# 12-SoC_POWER2.net
KiCad netlist of a schematic drawn in Altium Designer
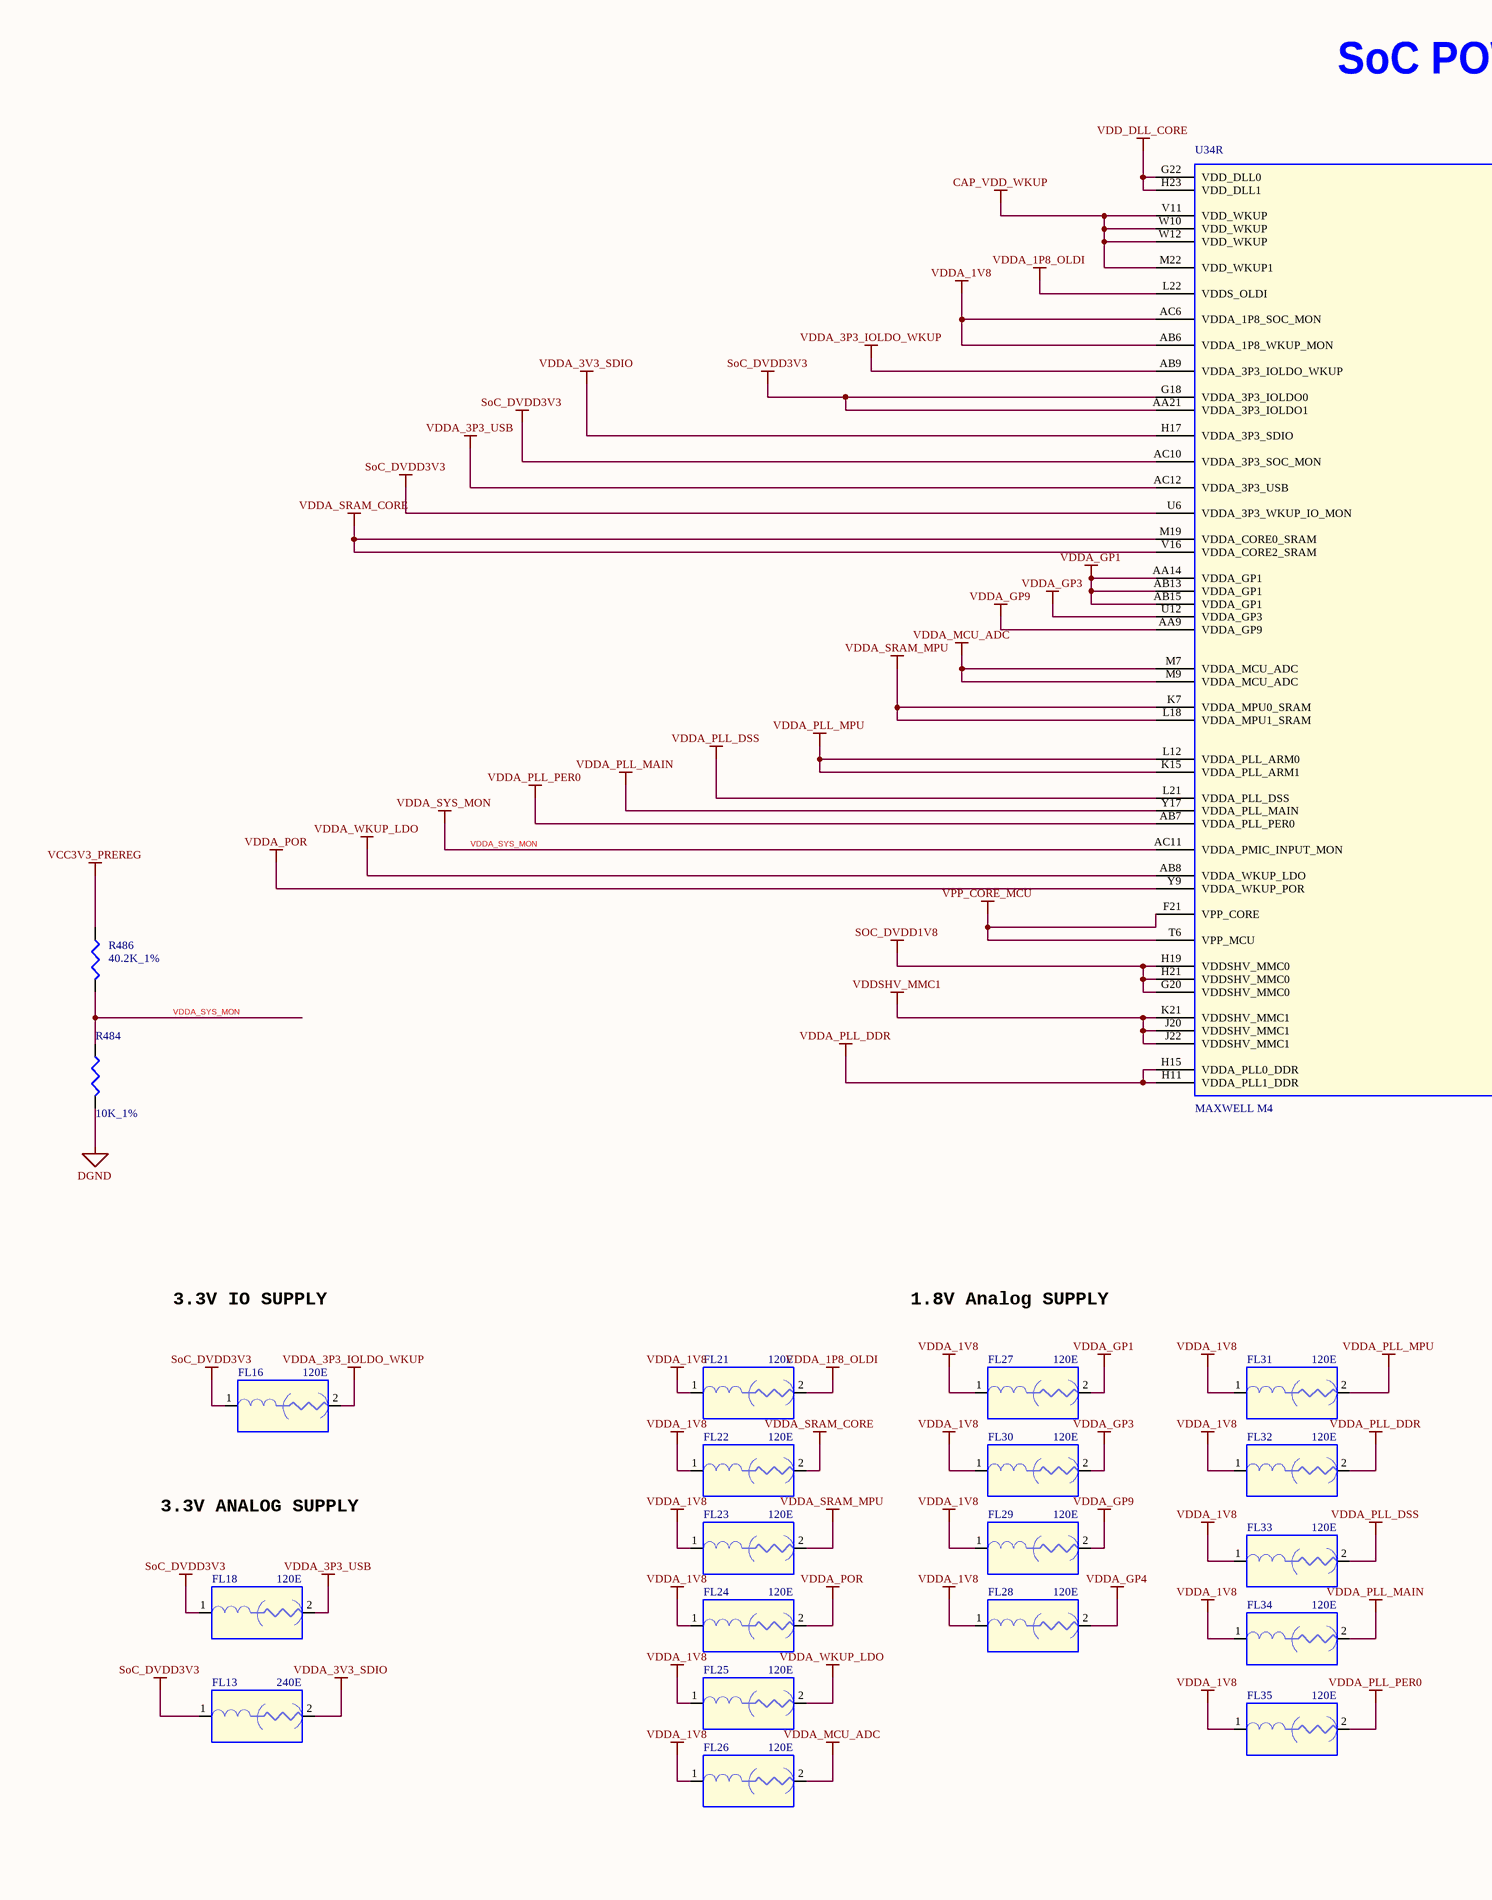
[diagram p0: 12-SoC POWER2.SchDoc, left]
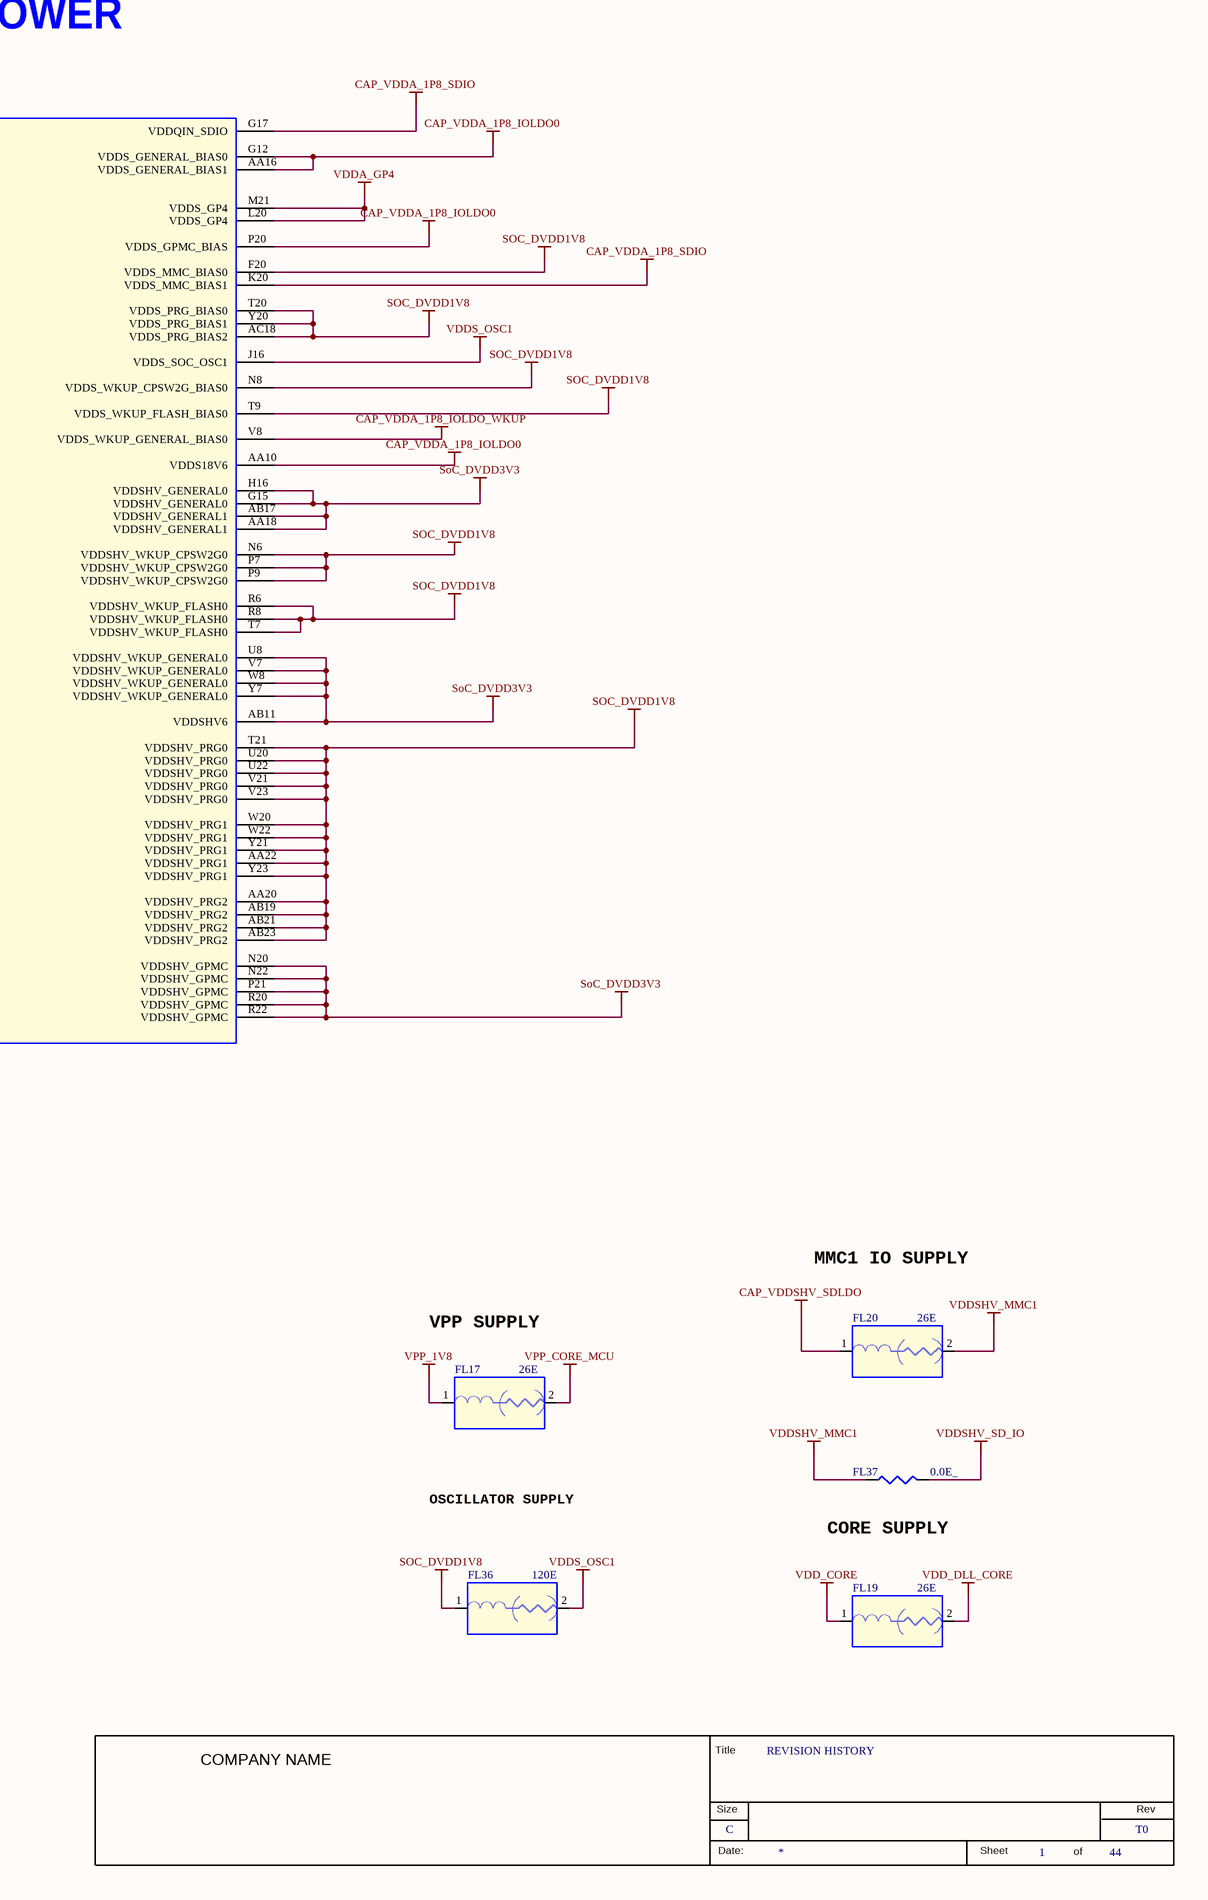
[diagram p1: 12-SoC POWER2.SchDoc, right]

(export (version "E")
  (design (tool "Eeschema 10.0.6"))
  (components
    (comp (ref "FL13")
      (value "240E")
      (footprint "EMIFIL_BLM03B_0201")
      (description "FERRITE CHIP 240E 350mA 0201")
      (fields
        (field (name "MISTRAL PART NO") "130014070021-R")
        (field (name "MFR_PART_NUMBER") "BLM03AX241SN1D")
      )
      (libsource (lib "*") (part "EMIFILTER_IND"))
    )
    (comp (ref "FL16")
      (value "120E")
      (footprint "EMIFIL_BLM18R_0603_1")
      (description "FERRITE BEAD 120E 2A 0603")
      (fields
        (field (name "MISTRAL PART NO") "130010060030-R")
        (field (name "MFR_PART_NUMBER") "BLM18EG121SN1D")
      )
      (libsource (lib "*") (part "EMIFILTER_IND"))
    )
    (comp (ref "FL17")
      (value "26E")
      (footprint "EMIFIL_BLM18K_0603")
      (description "FERRITE CHIP 26E 6A 0603")
      (fields
        (field (name "MISTRAL PART NO") "130012010003-R")
        (field (name "MFR_PART_NUMBER") "BLM18KG260TN1D")
      )
      (libsource (lib "*") (part "EMIFILTER_IND"))
    )
    (comp (ref "FL18")
      (value "120E")
      (footprint "EMIFIL_BLM18R_0603_1")
      (description "FERRITE BEAD 120E 2A 0603")
      (fields
        (field (name "MISTRAL PART NO") "130010060030-R")
        (field (name "MFR_PART_NUMBER") "BLM18EG121SN1D")
      )
      (libsource (lib "*") (part "EMIFILTER_IND"))
    )
    (comp (ref "FL19")
      (value "26E")
      (footprint "EMIFIL_BLM18K_0603")
      (description "FERRITE CHIP 26E 6A 0603")
      (fields (field (name "DISTRIBUTOR_PART_NUMBER") "490-5252-1-ND") (field (name "VOLTAGE") "NA"))
      (libsource (lib "*") (part "EMIFILTER_IND"))
    )
    (comp (ref "FL20")
      (value "26E")
      (footprint "EMIFIL_BLM18K_0603")
      (description "FERRITE CHIP 26E 6A 0603")
      (fields (field (name "DISTRIBUTOR_PART_NUMBER") "490-5252-1-ND") (field (name "VOLTAGE") "NA"))
      (libsource (lib "*") (part "EMIFILTER_IND"))
    )
    (comp (ref "FL21")
      (value "120E")
      (footprint "EMIFIL_BLM18R_0603_1")
      (description "FERRITE BEAD 120E 2A 0603")
      (fields
        (field (name "MISTRAL PART NO") "130010060030-R")
        (field (name "MFR_PART_NUMBER") "BLM18EG121SN1D")
      )
      (libsource (lib "*") (part "EMIFILTER_IND"))
    )
    (comp (ref "FL22")
      (value "120E")
      (footprint "EMIFIL_BLM18R_0603_1")
      (description "FERRITE BEAD 120E 2A 0603")
      (fields
        (field (name "MISTRAL PART NO") "130010060030-R")
        (field (name "MFR_PART_NUMBER") "BLM18EG121SN1D")
      )
      (libsource (lib "*") (part "EMIFILTER_IND"))
    )
    (comp (ref "FL23")
      (value "120E")
      (footprint "EMIFIL_BLM18R_0603_1")
      (description "FERRITE BEAD 120E 2A 0603")
      (fields
        (field (name "MISTRAL PART NO") "130010060030-R")
        (field (name "MFR_PART_NUMBER") "BLM18EG121SN1D")
      )
      (libsource (lib "*") (part "EMIFILTER_IND"))
    )
    (comp (ref "FL24")
      (value "120E")
      (footprint "EMIFIL_BLM18R_0603_1")
      (description "FERRITE BEAD 120E 2A 0603")
      (fields (field (name "DISTRIBUTOR_PART_NUMBER") "490-3991-1-ND") (field (name "VOLTAGE") "NA"))
      (libsource (lib "*") (part "EMIFILTER_IND"))
    )
    (comp (ref "FL25")
      (value "120E")
      (footprint "EMIFIL_BLM18R_0603_1")
      (description "FERRITE BEAD 120E 2A 0603")
      (fields
        (field (name "MISTRAL PART NO") "130010060030-R")
        (field (name "MFR_PART_NUMBER") "BLM18EG121SN1D")
      )
      (libsource (lib "*") (part "EMIFILTER_IND"))
    )
    (comp (ref "FL26")
      (value "120E")
      (footprint "EMIFIL_BLM18R_0603_1")
      (description "FERRITE BEAD 120E 2A 0603")
      (fields (field (name "DISTRIBUTOR_PART_NUMBER") "490-3991-1-ND") (field (name "VOLTAGE") "NA"))
      (libsource (lib "*") (part "EMIFILTER_IND"))
    )
    (comp (ref "FL27")
      (value "120E")
      (footprint "EMIFIL_BLM18R_0603_1")
      (description "FERRITE BEAD 120E 2A 0603")
      (fields
        (field (name "MISTRAL PART NO") "130010060030-R")
        (field (name "MFR_PART_NUMBER") "BLM18EG121SN1D")
      )
      (libsource (lib "*") (part "EMIFILTER_IND"))
    )
    (comp (ref "FL28")
      (value "120E")
      (footprint "EMIFIL_BLM18R_0603_1")
      (description "FERRITE BEAD 120E 2A 0603")
      (fields (field (name "DISTRIBUTOR_PART_NUMBER") "490-3991-1-ND") (field (name "VOLTAGE") "NA"))
      (libsource (lib "*") (part "EMIFILTER_IND"))
    )
    (comp (ref "FL29")
      (value "120E")
      (footprint "EMIFIL_BLM18R_0603_1")
      (description "FERRITE BEAD 120E 2A 0603")
      (fields (field (name "DISTRIBUTOR_PART_NUMBER") "490-3991-1-ND") (field (name "VOLTAGE") "NA"))
      (libsource (lib "*") (part "EMIFILTER_IND"))
    )
    (comp (ref "FL30")
      (value "120E")
      (footprint "EMIFIL_BLM18R_0603_1")
      (description "FERRITE BEAD 120E 2A 0603")
      (fields
        (field (name "MISTRAL PART NO") "130010060030-R")
        (field (name "MFR_PART_NUMBER") "BLM18EG121SN1D")
      )
      (libsource (lib "*") (part "EMIFILTER_IND"))
    )
    (comp (ref "FL31")
      (value "120E")
      (footprint "EMIFIL_BLM18R_0603_1")
      (description "FERRITE BEAD 120E 2A 0603")
      (fields (field (name "DISTRIBUTOR_PART_NUMBER") "490-3991-1-ND") (field (name "VOLTAGE") "NA"))
      (libsource (lib "*") (part "EMIFILTER_IND"))
    )
    (comp (ref "FL32")
      (value "120E")
      (footprint "EMIFIL_BLM18R_0603_1")
      (description "FERRITE BEAD 120E 2A 0603")
      (fields
        (field (name "MISTRAL PART NO") "130010060030-R")
        (field (name "MFR_PART_NUMBER") "BLM18EG121SN1D")
      )
      (libsource (lib "*") (part "EMIFILTER_IND"))
    )
    (comp (ref "FL33")
      (value "120E")
      (footprint "EMIFIL_BLM18R_0603_1")
      (description "FERRITE BEAD 120E 2A 0603")
      (fields
        (field (name "MISTRAL PART NO") "130010060030-R")
        (field (name "MFR_PART_NUMBER") "BLM18EG121SN1D")
      )
      (libsource (lib "*") (part "EMIFILTER_IND"))
    )
    (comp (ref "FL34")
      (value "120E")
      (footprint "EMIFIL_BLM18R_0603_1")
      (description "FERRITE BEAD 120E 2A 0603")
      (fields
        (field (name "MISTRAL PART NO") "130010060030-R")
        (field (name "MFR_PART_NUMBER") "BLM18EG121SN1D")
      )
      (libsource (lib "*") (part "EMIFILTER_IND"))
    )
    (comp (ref "FL35")
      (value "120E")
      (footprint "EMIFIL_BLM18R_0603_1")
      (description "FERRITE BEAD 120E 2A 0603")
      (fields
        (field (name "MISTRAL PART NO") "130010060030-R")
        (field (name "MFR_PART_NUMBER") "BLM18EG121SN1D")
      )
      (libsource (lib "*") (part "EMIFILTER_IND"))
    )
    (comp (ref "FL36")
      (value "120E")
      (footprint "EMIFIL_BLM18R_0603_1")
      (description "FERRITE BEAD 120E 2A 0603")
      (fields (field (name "DISTRIBUTOR_PART_NUMBER") "490-3991-1-ND") (field (name "VOLTAGE") "NA"))
      (libsource (lib "*") (part "EMIFILTER_IND"))
    )
    (comp (ref "FL37")
      (value "0.0E_")
      (footprint "RES0603")
      (description "RES 0.0E 1/10W 0603")
      (fields
        (field (name "MISTRAL PART NO") "110010020006-P")
        (field (name "MFR_PART_NUMBER") "CRCW06030000Z0EA")
      )
      (libsource (lib "*") (part "RESISTOR"))
    )
    (comp (ref "R484")
      (value "10K_1%")
      (footprint "RES0402_0-5")
      (description "RES 10K 1/16W 1% 0402")
      (fields (field (name "DISTRIBUTOR_PART_NUMBER") "311-10.0KLRTR-ND") (field (name "VOLTAGE") "NA"))
      (libsource (lib "*") (part "RESISTOR_Dup5"))
    )
    (comp (ref "R486")
      (value "40.2K_1%")
      (footprint "RES0402_0-5")
      (description "RES 40.2K 1/16W 1% 0402")
      (fields (field (name "DISTRIBUTOR_PART_NUMBER") "311-40.2KLRDKR-ND") (field (name "VOLTAGE") "NA"))
      (libsource (lib "*") (part "RESISTOR_Dup5"))
    )
    (comp (ref "U34")
      (value "MAXWELL M4")
      (footprint "BGA784_31-49_910X910_1-7")
      (description "IC MAXWELL MICRO CONTROLLER UNIT BGA784")
      (fields (field (name "DISTRIBUTOR_PART_NUMBER") "NA") (field (name "MFR_PART_NUMBER") "MAXWELL M4_EVM"))
      (libsource (lib "*") (part "AM654X_BGA784"))
    )
  )
  (nets
    (net (code "1") (name "CAP_VDDA_1P8_IOLDO0") (class "Default")
      (node (ref "U34") (pin "AA10") (pinfunction "VDDS18V6_AA10") (pintype "power_in"))
      (node (ref "U34") (pin "AA16") (pinfunction "VDDS_GENERAL_BIAS1_AA16") (pintype "power_in"))
      (node (ref "U34") (pin "G12") (pinfunction "VDDS_GENERAL_BIAS0_G12") (pintype "power_in"))
      (node (ref "U34") (pin "P20") (pinfunction "VDDS_GPMC_BIAS_P20") (pintype "power_in"))
    )
    (net (code "2") (name "CAP_VDDA_1P8_IOLDO_WKUP") (class "Default")
      (node (ref "U34") (pin "V8") (pinfunction "VDDS_WKUP_GENERAL_BIAS0_V8") (pintype "power_in"))
    )
    (net (code "3") (name "CAP_VDDA_1P8_SDIO") (class "Default")
      (node (ref "U34") (pin "G17") (pinfunction "VDDQIN_SDIO_G17") (pintype "power_in"))
      (node (ref "U34") (pin "K20") (pinfunction "VDDS_MMC_BIAS1_K20") (pintype "power_in"))
    )
    (net (code "4") (name "CAP_VDDSHV_SDLDO") (class "Default")
      (node (ref "FL20") (pin "1") (pinfunction "1_1") (pintype "passive"))
    )
    (net (code "5") (name "CAP_VDD_WKUP") (class "Default")
      (node (ref "U34") (pin "M22") (pinfunction "VDD_WKUP1_M22") (pintype "power_in"))
      (node (ref "U34") (pin "V11") (pinfunction "VDD_WKUP_V11") (pintype "power_in"))
      (node (ref "U34") (pin "W10") (pinfunction "VDD_WKUP_W10") (pintype "power_in"))
      (node (ref "U34") (pin "W12") (pinfunction "VDD_WKUP_W12") (pintype "power_in"))
    )
    (net (code "6") (name "DGND") (class "Default")
      (node (ref "R484") (pin "2") (pinfunction "2_2") (pintype "passive"))
    )
    (net (code "7") (name "SOC_DVDD1V8") (class "Default")
      (node (ref "FL36") (pin "1") (pinfunction "1_1") (pintype "passive"))
      (node (ref "U34") (pin "AA20") (pinfunction "VDDSHV_PRG2_AA20") (pintype "power_in"))
      (node (ref "U34") (pin "AA22") (pinfunction "VDDSHV_PRG1_AA22") (pintype "power_in"))
      (node (ref "U34") (pin "AB19") (pinfunction "VDDSHV_PRG2_AB19") (pintype "power_in"))
      (node (ref "U34") (pin "AB21") (pinfunction "VDDSHV_PRG2_AB21") (pintype "power_in"))
      (node (ref "U34") (pin "AB23") (pinfunction "VDDSHV_PRG2_AB23") (pintype "power_in"))
      (node (ref "U34") (pin "AC18") (pinfunction "VDDS_PRG_BIAS2_AC18") (pintype "power_in"))
      (node (ref "U34") (pin "F20") (pinfunction "VDDS_MMC_BIAS0_F20") (pintype "power_in"))
      (node (ref "U34") (pin "G20") (pinfunction "VDDSHV_MMC0_G20") (pintype "power_in"))
      (node (ref "U34") (pin "H19") (pinfunction "VDDSHV_MMC0_H19") (pintype "power_in"))
      (node (ref "U34") (pin "H21") (pinfunction "VDDSHV_MMC0_H21") (pintype "power_in"))
      (node (ref "U34") (pin "N6") (pinfunction "VDDSHV_WKUP_CPSW2G0_N6") (pintype "power_in"))
      (node (ref "U34") (pin "N8") (pinfunction "VDDS_WKUP_CPSW2G_BIAS0_N8") (pintype "power_in"))
      (node (ref "U34") (pin "P7") (pinfunction "VDDSHV_WKUP_CPSW2G0_P7") (pintype "power_in"))
      (node (ref "U34") (pin "P9") (pinfunction "VDDSHV_WKUP_CPSW2G0_P9") (pintype "power_in"))
      (node (ref "U34") (pin "R6") (pinfunction "VDDSHV_WKUP_FLASH0_R6") (pintype "power_in"))
      (node (ref "U34") (pin "R8") (pinfunction "VDDSHV_WKUP_FLASH0_R8") (pintype "power_in"))
      (node (ref "U34") (pin "T20") (pinfunction "VDDS_PRG_BIAS0_T20") (pintype "power_in"))
      (node (ref "U34") (pin "T21") (pinfunction "VDDSHV_PRG0_T21") (pintype "power_in"))
      (node (ref "U34") (pin "T7") (pinfunction "VDDSHV_WKUP_FLASH0_T7") (pintype "power_in"))
      (node (ref "U34") (pin "T9") (pinfunction "VDDS_WKUP_FLASH_BIAS0_T9") (pintype "power_in"))
      (node (ref "U34") (pin "U20") (pinfunction "VDDSHV_PRG0_U20") (pintype "power_in"))
      (node (ref "U34") (pin "U22") (pinfunction "VDDSHV_PRG0_U22") (pintype "power_in"))
      (node (ref "U34") (pin "V21") (pinfunction "VDDSHV_PRG0_V21") (pintype "power_in"))
      (node (ref "U34") (pin "V23") (pinfunction "VDDSHV_PRG0_V23") (pintype "power_in"))
      (node (ref "U34") (pin "W20") (pinfunction "VDDSHV_PRG1_W20") (pintype "power_in"))
      (node (ref "U34") (pin "W22") (pinfunction "VDDSHV_PRG1_W22") (pintype "power_in"))
      (node (ref "U34") (pin "Y20") (pinfunction "VDDS_PRG_BIAS1_Y20") (pintype "power_in"))
      (node (ref "U34") (pin "Y21") (pinfunction "VDDSHV_PRG1_Y21") (pintype "power_in"))
      (node (ref "U34") (pin "Y23") (pinfunction "VDDSHV_PRG1_Y23") (pintype "power_in"))
    )
    (net (code "8") (name "SoC_DVDD3V3") (class "Default")
      (node (ref "FL13") (pin "1") (pinfunction "1_1") (pintype "passive"))
      (node (ref "FL16") (pin "1") (pinfunction "1_1") (pintype "passive"))
      (node (ref "FL18") (pin "1") (pinfunction "1_1") (pintype "passive"))
      (node (ref "U34") (pin "AA18") (pinfunction "VDDSHV_GENERAL1_AA18") (pintype "power_in"))
      (node (ref "U34") (pin "AA21") (pinfunction "VDDA_3P3_IOLDO1_AA21") (pintype "power_in"))
      (node (ref "U34") (pin "AB11") (pinfunction "VDDSHV6_AB11") (pintype "power_in"))
      (node (ref "U34") (pin "AB17") (pinfunction "VDDSHV_GENERAL1_AB17") (pintype "power_in"))
      (node (ref "U34") (pin "AC10") (pinfunction "VDDA_3P3_SOC_MON_AC10") (pintype "power_in"))
      (node (ref "U34") (pin "G15") (pinfunction "VDDSHV_GENERAL0_G15") (pintype "power_in"))
      (node (ref "U34") (pin "G18") (pinfunction "VDDA_3P3_IOLDO0_G18") (pintype "power_in"))
      (node (ref "U34") (pin "H16") (pinfunction "VDDSHV_GENERAL0_H16") (pintype "power_in"))
      (node (ref "U34") (pin "N20") (pinfunction "VDDSHV_GPMC_N20") (pintype "power_in"))
      (node (ref "U34") (pin "N22") (pinfunction "VDDSHV_GPMC_N22") (pintype "power_in"))
      (node (ref "U34") (pin "P21") (pinfunction "VDDSHV_GPMC_P21") (pintype "power_in"))
      (node (ref "U34") (pin "R20") (pinfunction "VDDSHV_GPMC_R20") (pintype "power_in"))
      (node (ref "U34") (pin "R22") (pinfunction "VDDSHV_GPMC_R22") (pintype "power_in"))
      (node (ref "U34") (pin "U6") (pinfunction "VDDA_3P3_WKUP_IO_MON_U6") (pintype "power_in"))
      (node (ref "U34") (pin "U8") (pinfunction "VDDSHV_WKUP_GENERAL0_U8") (pintype "power_in"))
      (node (ref "U34") (pin "V7") (pinfunction "VDDSHV_WKUP_GENERAL0_V7") (pintype "power_in"))
      (node (ref "U34") (pin "W8") (pinfunction "VDDSHV_WKUP_GENERAL0_W8") (pintype "power_in"))
      (node (ref "U34") (pin "Y7") (pinfunction "VDDSHV_WKUP_GENERAL0_Y7") (pintype "power_in"))
    )
    (net (code "9") (name "VCC3V3_PREREG") (class "Default")
      (node (ref "R486") (pin "1") (pinfunction "1_1") (pintype "passive"))
    )
    (net (code "10") (name "VDDA_1P8_OLDI") (class "Default")
      (node (ref "FL21") (pin "2") (pinfunction "2_2") (pintype "passive"))
      (node (ref "U34") (pin "L22") (pinfunction "VDDS_OLDI_L22") (pintype "power_in"))
    )
    (net (code "11") (name "VDDA_1V8") (class "Default")
      (node (ref "FL21") (pin "1") (pinfunction "1_1") (pintype "passive"))
      (node (ref "FL22") (pin "1") (pinfunction "1_1") (pintype "passive"))
      (node (ref "FL23") (pin "1") (pinfunction "1_1") (pintype "passive"))
      (node (ref "FL24") (pin "1") (pinfunction "1_1") (pintype "passive"))
      (node (ref "FL25") (pin "1") (pinfunction "1_1") (pintype "passive"))
      (node (ref "FL26") (pin "1") (pinfunction "1_1") (pintype "passive"))
      (node (ref "FL27") (pin "1") (pinfunction "1_1") (pintype "passive"))
      (node (ref "FL28") (pin "1") (pinfunction "1_1") (pintype "passive"))
      (node (ref "FL29") (pin "1") (pinfunction "1_1") (pintype "passive"))
      (node (ref "FL30") (pin "1") (pinfunction "1_1") (pintype "passive"))
      (node (ref "FL31") (pin "1") (pinfunction "1_1") (pintype "passive"))
      (node (ref "FL32") (pin "1") (pinfunction "1_1") (pintype "passive"))
      (node (ref "FL33") (pin "1") (pinfunction "1_1") (pintype "passive"))
      (node (ref "FL34") (pin "1") (pinfunction "1_1") (pintype "passive"))
      (node (ref "FL35") (pin "1") (pinfunction "1_1") (pintype "passive"))
      (node (ref "U34") (pin "AB6") (pinfunction "VDDA_1P8_WKUP_MON_AB6") (pintype "power_in"))
      (node (ref "U34") (pin "AC6") (pinfunction "VDDA_1P8_SOC_MON_AC6") (pintype "power_in"))
    )
    (net (code "12") (name "VDDA_3P3_IOLDO_WKUP") (class "Default")
      (node (ref "FL16") (pin "2") (pinfunction "2_2") (pintype "passive"))
      (node (ref "U34") (pin "AB9") (pinfunction "VDDA_3P3_IOLDO_WKUP_AB9") (pintype "power_in"))
    )
    (net (code "13") (name "VDDA_3P3_USB") (class "Default")
      (node (ref "FL18") (pin "2") (pinfunction "2_2") (pintype "passive"))
      (node (ref "U34") (pin "AC12") (pinfunction "VDDA_3P3_USB_AC12") (pintype "power_in"))
    )
    (net (code "14") (name "VDDA_3V3_SDIO") (class "Default")
      (node (ref "FL13") (pin "2") (pinfunction "2_2") (pintype "passive"))
      (node (ref "U34") (pin "H17") (pinfunction "VDDA_3P3_SDIO_H17") (pintype "power_in"))
    )
    (net (code "15") (name "VDDA_GP1") (class "Default")
      (node (ref "FL27") (pin "2") (pinfunction "2_2") (pintype "passive"))
      (node (ref "U34") (pin "AA14") (pinfunction "VDDA_GP1_AA14") (pintype "power_in"))
      (node (ref "U34") (pin "AB13") (pinfunction "VDDA_GP1_AB13") (pintype "power_in"))
      (node (ref "U34") (pin "AB15") (pinfunction "VDDA_GP1_AB15") (pintype "power_in"))
    )
    (net (code "16") (name "VDDA_GP3") (class "Default")
      (node (ref "FL30") (pin "2") (pinfunction "2_2") (pintype "passive"))
      (node (ref "U34") (pin "U12") (pinfunction "VDDA_GP3_U12") (pintype "power_in"))
    )
    (net (code "17") (name "VDDA_GP4") (class "Default")
      (node (ref "FL28") (pin "2") (pinfunction "2_2") (pintype "passive"))
      (node (ref "U34") (pin "L20") (pinfunction "VDDS_GP4_L20") (pintype "power_in"))
      (node (ref "U34") (pin "M21") (pinfunction "VDDS_GP4_M21") (pintype "power_in"))
    )
    (net (code "18") (name "VDDA_GP9") (class "Default")
      (node (ref "FL29") (pin "2") (pinfunction "2_2") (pintype "passive"))
      (node (ref "U34") (pin "AA9") (pinfunction "VDDA_GP9_AA9") (pintype "power_in"))
    )
    (net (code "19") (name "VDDA_MCU_ADC") (class "Default")
      (node (ref "FL26") (pin "2") (pinfunction "2_2") (pintype "passive"))
      (node (ref "U34") (pin "M7") (pinfunction "VDDA_MCU_ADC_M7") (pintype "power_in"))
      (node (ref "U34") (pin "M9") (pinfunction "VDDA_MCU_ADC_M9") (pintype "power_in"))
    )
    (net (code "20") (name "VDDA_PLL_DDR") (class "Default")
      (node (ref "FL32") (pin "2") (pinfunction "2_2") (pintype "passive"))
      (node (ref "U34") (pin "H11") (pinfunction "VDDA_PLL1_DDR_H11") (pintype "power_in"))
      (node (ref "U34") (pin "H15") (pinfunction "VDDA_PLL0_DDR_H15") (pintype "power_in"))
    )
    (net (code "21") (name "VDDA_PLL_DSS") (class "Default")
      (node (ref "FL33") (pin "2") (pinfunction "2_2") (pintype "passive"))
      (node (ref "U34") (pin "L21") (pinfunction "VDDA_PLL_DSS_L21") (pintype "power_in"))
    )
    (net (code "22") (name "VDDA_PLL_MAIN") (class "Default")
      (node (ref "FL34") (pin "2") (pinfunction "2_2") (pintype "passive"))
      (node (ref "U34") (pin "Y17") (pinfunction "VDDA_PLL_MAIN_Y17") (pintype "power_in"))
    )
    (net (code "23") (name "VDDA_PLL_MPU") (class "Default")
      (node (ref "FL31") (pin "2") (pinfunction "2_2") (pintype "passive"))
      (node (ref "U34") (pin "K15") (pinfunction "VDDA_PLL_ARM1_K15") (pintype "power_in"))
      (node (ref "U34") (pin "L12") (pinfunction "VDDA_PLL_ARM0_L12") (pintype "power_in"))
    )
    (net (code "24") (name "VDDA_PLL_PER0") (class "Default")
      (node (ref "FL35") (pin "2") (pinfunction "2_2") (pintype "passive"))
      (node (ref "U34") (pin "AB7") (pinfunction "VDDA_PLL_PER0_AB7") (pintype "power_in"))
    )
    (net (code "25") (name "VDDA_POR") (class "Default")
      (node (ref "FL24") (pin "2") (pinfunction "2_2") (pintype "passive"))
      (node (ref "U34") (pin "Y9") (pinfunction "VDDA_WKUP_POR_Y9") (pintype "power_in"))
    )
    (net (code "26") (name "VDDA_SRAM_CORE") (class "Default")
      (node (ref "FL22") (pin "2") (pinfunction "2_2") (pintype "passive"))
      (node (ref "U34") (pin "M19") (pinfunction "VDDA_CORE0_SRAM_M19") (pintype "power_in"))
      (node (ref "U34") (pin "V16") (pinfunction "VDDA_CORE2_SRAM_V16") (pintype "power_in"))
    )
    (net (code "27") (name "VDDA_SRAM_MPU") (class "Default")
      (node (ref "FL23") (pin "2") (pinfunction "2_2") (pintype "passive"))
      (node (ref "U34") (pin "K7") (pinfunction "VDDA_MPU0_SRAM_K7") (pintype "power_in"))
      (node (ref "U34") (pin "L18") (pinfunction "VDDA_MPU1_SRAM_L18") (pintype "power_in"))
    )
    (net (code "28") (name "VDDA_SYS_MON") (class "Default")
      (node (ref "R484") (pin "1") (pinfunction "1_1") (pintype "passive"))
      (node (ref "R486") (pin "2") (pinfunction "2_2") (pintype "passive"))
      (node (ref "U34") (pin "AC11") (pinfunction "VDDA_PMIC_INPUT_MON_AC11") (pintype "power_in"))
    )
    (net (code "29") (name "VDDA_WKUP_LDO") (class "Default")
      (node (ref "FL25") (pin "2") (pinfunction "2_2") (pintype "passive"))
      (node (ref "U34") (pin "AB8") (pinfunction "VDDA_WKUP_LDO_AB8") (pintype "power_in"))
    )
    (net (code "30") (name "VDDSHV_MMC1") (class "Default")
      (node (ref "FL20") (pin "2") (pinfunction "2_2") (pintype "passive"))
      (node (ref "FL37") (pin "1") (pinfunction "1_1") (pintype "passive"))
      (node (ref "U34") (pin "J20") (pinfunction "VDDSHV_MMC1_J20") (pintype "power_in"))
      (node (ref "U34") (pin "J22") (pinfunction "VDDSHV_MMC1_J22") (pintype "power_in"))
      (node (ref "U34") (pin "K21") (pinfunction "VDDSHV_MMC1_K21") (pintype "power_in"))
    )
    (net (code "31") (name "VDDSHV_SD_IO") (class "Default")
      (node (ref "FL37") (pin "2") (pinfunction "2_2") (pintype "passive"))
    )
    (net (code "32") (name "VDDS_OSC1") (class "Default")
      (node (ref "FL36") (pin "2") (pinfunction "2_2") (pintype "passive"))
      (node (ref "U34") (pin "J16") (pinfunction "VDDS_SOC_OSC1_J16") (pintype "power_in"))
    )
    (net (code "33") (name "VDD_CORE") (class "Default")
      (node (ref "FL19") (pin "1") (pinfunction "1_1") (pintype "passive"))
    )
    (net (code "34") (name "VDD_DLL_CORE") (class "Default")
      (node (ref "FL19") (pin "2") (pinfunction "2_2") (pintype "passive"))
      (node (ref "U34") (pin "G22") (pinfunction "VDD_DLL0_G22") (pintype "power_in"))
      (node (ref "U34") (pin "H23") (pinfunction "VDD_DLL1_H23") (pintype "power_in"))
    )
    (net (code "35") (name "VPP_1V8") (class "Default")
      (node (ref "FL17") (pin "1") (pinfunction "1_1") (pintype "passive"))
    )
    (net (code "36") (name "VPP_CORE_MCU") (class "Default")
      (node (ref "FL17") (pin "2") (pinfunction "2_2") (pintype "passive"))
      (node (ref "U34") (pin "F21") (pinfunction "VPP_CORE_F21") (pintype "power_in"))
      (node (ref "U34") (pin "T6") (pinfunction "VPP_MCU_T6") (pintype "power_in"))
    )
  )
)
